# circuit-board.net
KiCad netlist of a schematic drawn in EAGLE
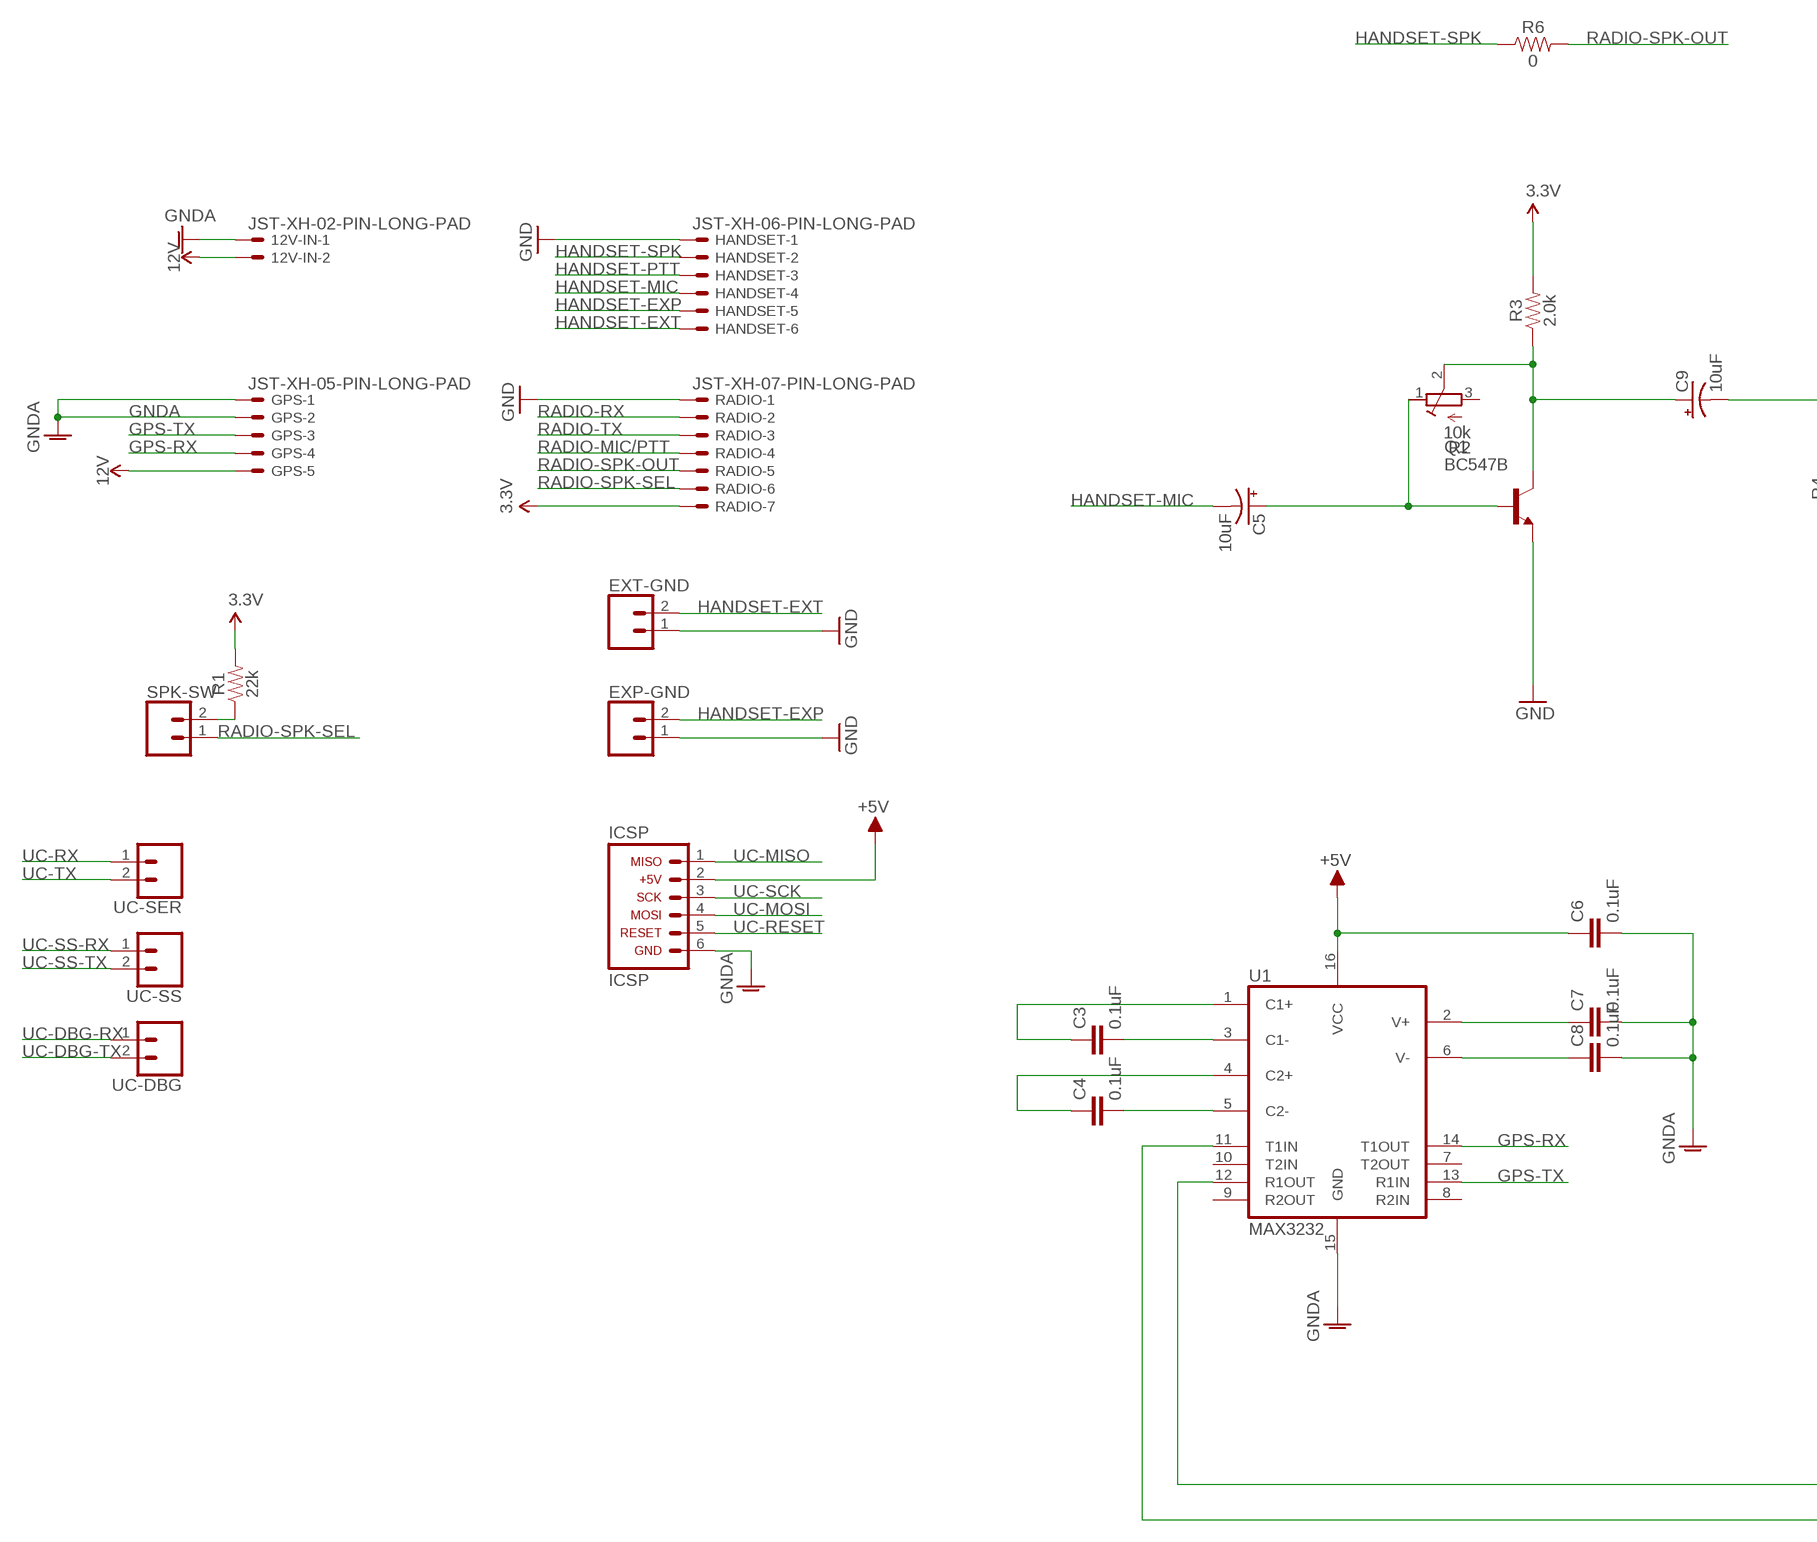
[diagram p0: schematic, sheet 1, part 1 of 2]
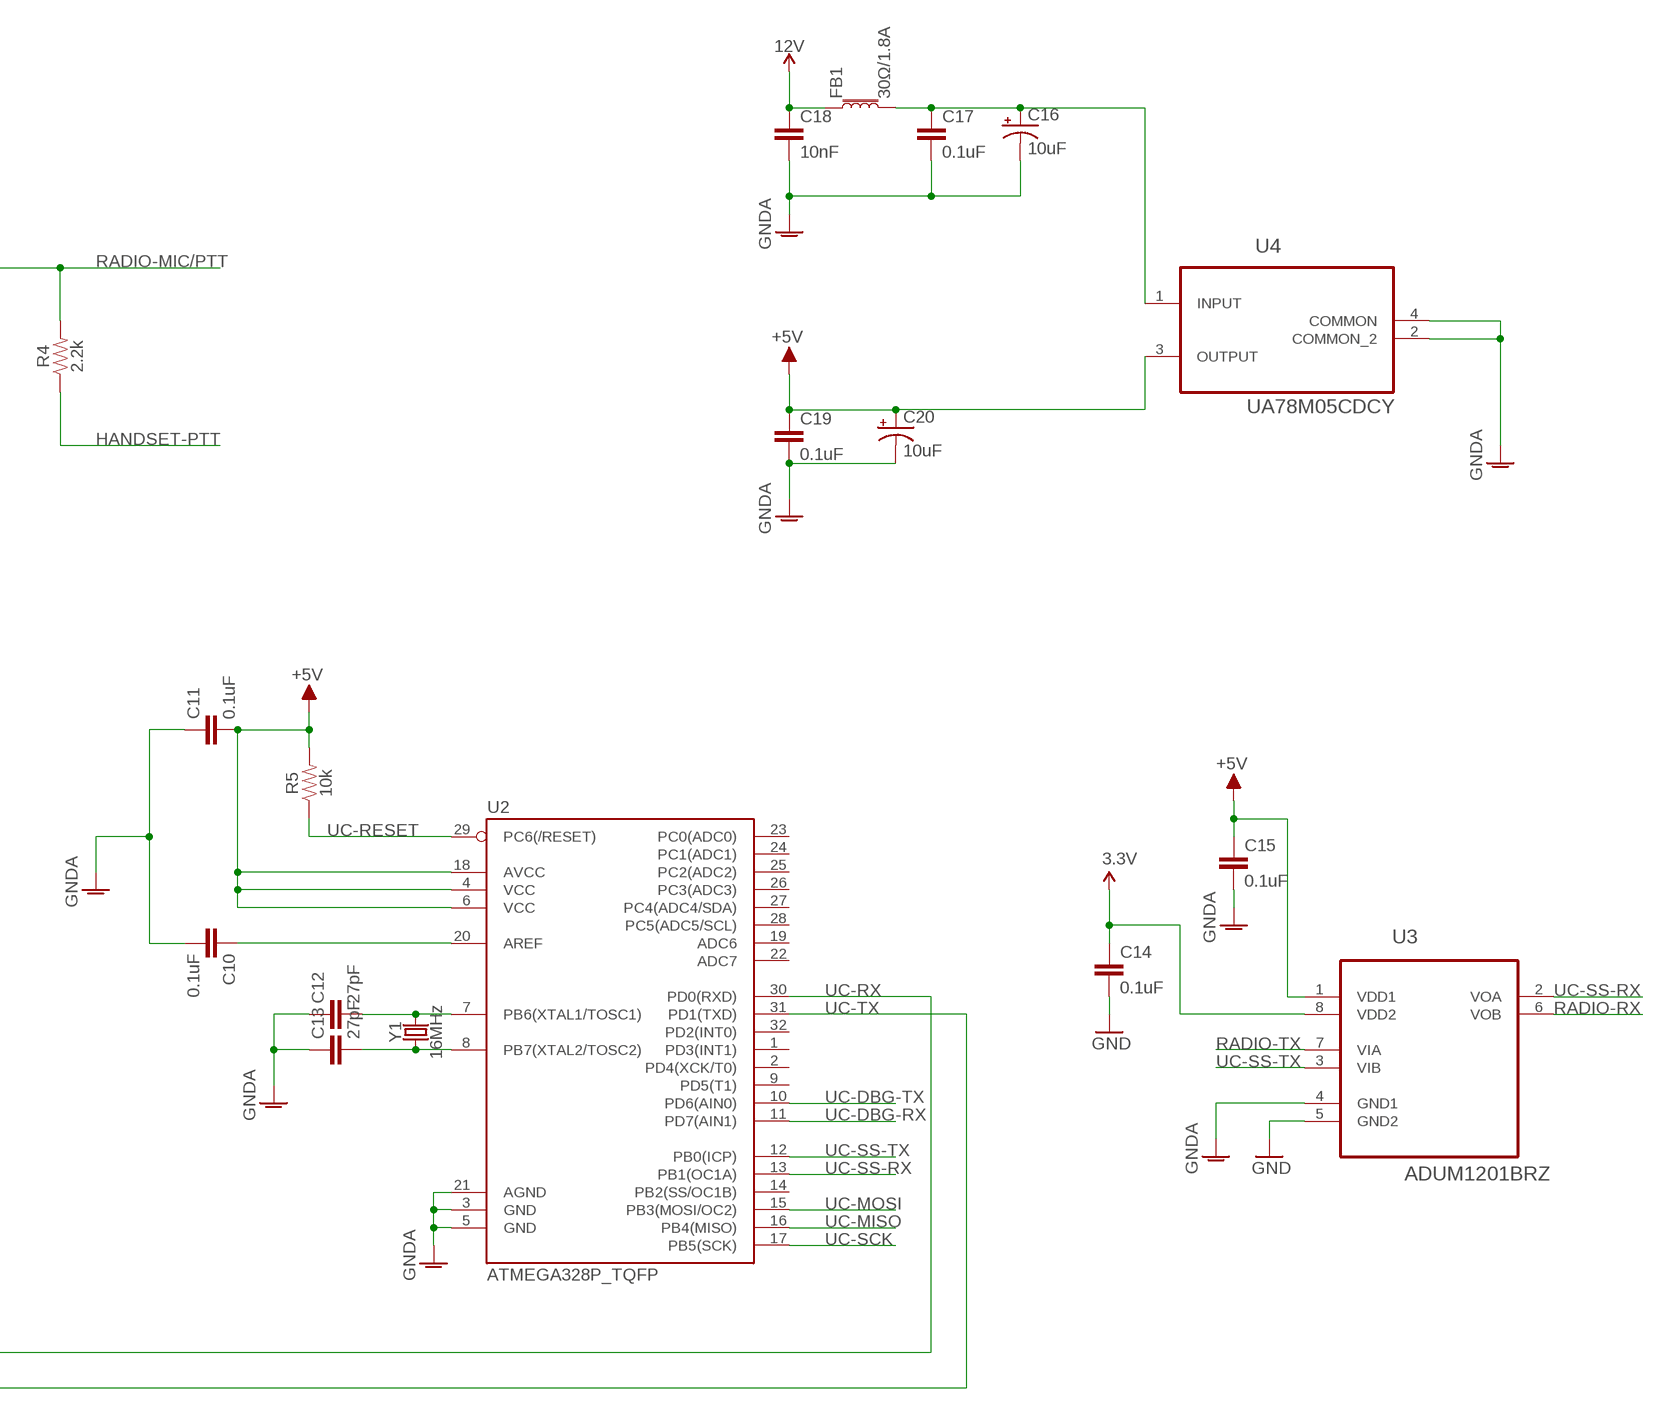
[diagram p1: schematic, sheet 1, part 2 of 2]

(export (version "E")
  (design (tool "Eeschema 10.0.6"))
  (components
    (comp (ref "12V-IN")
      (value "JST-XH-02-PIN-LONG-PAD")
      (footprint "eagle-import:JST-XH-02-PACKAGE-LONG-PAD")
      (libsource (lib "eagle-import") (part "JST-XH-02-PIN-LONG-PAD"))
    )
    (comp (ref "C3")
      (value "0.1uF")
      (footprint "eagle-import:0603")
      (libsource (lib "eagle-import") (part "0.1UF-0603-25V-5%"))
    )
    (comp (ref "C4")
      (value "0.1uF")
      (footprint "eagle-import:0603")
      (libsource (lib "eagle-import") (part "0.1UF-0603-25V-5%"))
    )
    (comp (ref "C5")
      (value "10uF")
      (footprint "eagle-import:E2,5-5")
      (libsource (lib "eagle-import") (part "CPOL-USE2.5-5"))
    )
    (comp (ref "C6")
      (value "0.1uF")
      (footprint "eagle-import:0603")
      (libsource (lib "eagle-import") (part "0.1UF-0603-25V-5%"))
    )
    (comp (ref "C7")
      (value "0.1uF")
      (footprint "eagle-import:0603")
      (libsource (lib "eagle-import") (part "0.1UF-0603-25V-5%"))
    )
    (comp (ref "C8")
      (value "0.1uF")
      (footprint "eagle-import:0603")
      (libsource (lib "eagle-import") (part "0.1UF-0603-25V-5%"))
    )
    (comp (ref "C9")
      (value "10uF")
      (footprint "eagle-import:E2,5-5")
      (libsource (lib "eagle-import") (part "CPOL-USE2.5-5"))
    )
    (comp (ref "C10")
      (value "0.1uF")
      (footprint "eagle-import:0603")
      (libsource (lib "eagle-import") (part "0.1UF-0603-25V-5%"))
    )
    (comp (ref "C11")
      (value "0.1uF")
      (footprint "eagle-import:0603")
      (libsource (lib "eagle-import") (part "0.1UF-0603-25V-5%"))
    )
    (comp (ref "C12")
      (value "27pF")
      (footprint "eagle-import:0603")
      (libsource (lib "eagle-import") (part "27PF-0603-50V-5%"))
    )
    (comp (ref "C13")
      (value "27pF")
      (footprint "eagle-import:0603")
      (libsource (lib "eagle-import") (part "27PF-0603-50V-5%"))
    )
    (comp (ref "C14")
      (value "0.1uF")
      (footprint "eagle-import:0603")
      (libsource (lib "eagle-import") (part "0.1UF-0603-25V-5%"))
    )
    (comp (ref "C15")
      (value "0.1uF")
      (footprint "eagle-import:0603")
      (libsource (lib "eagle-import") (part "0.1UF-0603-25V-5%"))
    )
    (comp (ref "C16")
      (value "10uF")
      (footprint "eagle-import:E2,5-5")
      (libsource (lib "eagle-import") (part "CPOL-USE2.5-5"))
    )
    (comp (ref "C17")
      (value "0.1uF")
      (footprint "eagle-import:0603")
      (libsource (lib "eagle-import") (part "0.1UF-0603-25V-5%"))
    )
    (comp (ref "C18")
      (value "10nF")
      (footprint "eagle-import:0603")
      (libsource (lib "eagle-import") (part "10NF-0603-50V-10%"))
    )
    (comp (ref "C19")
      (value "0.1uF")
      (footprint "eagle-import:0603")
      (libsource (lib "eagle-import") (part "0.1UF-0603-25V-5%"))
    )
    (comp (ref "C20")
      (value "10uF")
      (footprint "eagle-import:E2,5-5")
      (libsource (lib "eagle-import") (part "CPOL-USE2.5-5"))
    )
    (comp (ref "EXP-GND")
      (value "CONN_02")
      (footprint "eagle-import:1X02")
      (libsource (lib "eagle-import") (part "CONN_02"))
    )
    (comp (ref "EXT-GND")
      (value "CONN_02")
      (footprint "eagle-import:1X02")
      (libsource (lib "eagle-import") (part "CONN_02"))
    )
    (comp (ref "FB1")
      (value "30Ω/1.8A")
      (footprint "eagle-import:0603")
      (libsource (lib "eagle-import") (part "FERRITE_BEAD-0603"))
    )
    (comp (ref "GPS")
      (value "JST-XH-05-PIN-LONG-PAD")
      (footprint "eagle-import:JST-XH-05-PACKAGE-LONG-PAD")
      (libsource (lib "eagle-import") (part "JST-XH-05-PIN-LONG-PAD"))
    )
    (comp (ref "HANDSET")
      (value "JST-XH-06-PIN-LONG-PAD")
      (footprint "eagle-import:JST-XH-06-PACKAGE-LONG-PAD")
      (libsource (lib "eagle-import") (part "JST-XH-06-PIN-LONG-PAD"))
    )
    (comp (ref "ICSP")
      (value "ARDUINO_CONN-ICSP")
      (footprint "eagle-import:CONN-2X03")
      (libsource (lib "eagle-import") (part "ARDUINO_CONN-ICSP"))
    )
    (comp (ref "Q1")
      (value "BC547B")
      (footprint "eagle-import:TO92")
      (libsource (lib "eagle-import") (part "BC547B"))
    )
    (comp (ref "R1")
      (value "22k")
      (footprint "eagle-import:0603")
      (libsource (lib "eagle-import") (part "22KOHM-0603-1/10W-1%"))
    )
    (comp (ref "R2")
      (value "10k")
      (footprint "eagle-import:RTRIMT93YA")
      (libsource (lib "eagle-import") (part "R-TRIMMT93YA"))
    )
    (comp (ref "R3")
      (value "2.0k")
      (footprint "eagle-import:0603")
      (libsource (lib "eagle-import") (part "2.0KOHM-0603-1/10W-5%"))
    )
    (comp (ref "R4")
      (value "2.2k")
      (footprint "eagle-import:0603")
      (libsource (lib "eagle-import") (part "2.2KOHM-0603-1/10W-1%"))
    )
    (comp (ref "R5")
      (value "10k")
      (footprint "eagle-import:0603")
      (libsource (lib "eagle-import") (part "10KOHM-0603-1/10W-1%"))
    )
    (comp (ref "R6")
      (value "0")
      (footprint "eagle-import:0603")
      (libsource (lib "eagle-import") (part "0OHM-0603-1/10W-5%"))
    )
    (comp (ref "RADIO")
      (value "JST-XH-07-PIN-LONG-PAD")
      (footprint "eagle-import:JST-XH-07-PACKAGE-LONG-PAD")
      (libsource (lib "eagle-import") (part "JST-XH-07-PIN-LONG-PAD"))
    )
    (comp (ref "SPK-SW")
      (value "CONN_02")
      (footprint "eagle-import:1X02")
      (libsource (lib "eagle-import") (part "CONN_02"))
    )
    (comp (ref "U1")
      (value "MAX3232")
      (footprint "eagle-import:SO16")
      (libsource (lib "eagle-import") (part "MAX2323SOIC16"))
    )
    (comp (ref "U2")
      (value "ATMEGA328P_TQFP")
      (footprint "eagle-import:TQFP32-08")
      (libsource (lib "eagle-import") (part "ATMEGA328P_TQFP"))
    )
    (comp (ref "U3")
      (value "ADUM1201BRZ")
      (footprint "eagle-import:SOIC127P600X175-8N")
      (libsource (lib "eagle-import") (part "ADUM1201BRZ"))
    )
    (comp (ref "U4")
      (value "UA78M05CDCY")
      (footprint "eagle-import:SOT230P700X180-4N")
      (libsource (lib "eagle-import") (part "UA78M05CDCY"))
    )
    (comp (ref "UC-DBG")
      (value "CONN_02")
      (footprint "eagle-import:1X02")
      (libsource (lib "eagle-import") (part "CONN_02"))
    )
    (comp (ref "UC-SER")
      (value "CONN_02")
      (footprint "eagle-import:1X02")
      (libsource (lib "eagle-import") (part "CONN_02"))
    )
    (comp (ref "UC-SS")
      (value "CONN_02")
      (footprint "eagle-import:1X02")
      (libsource (lib "eagle-import") (part "CONN_02"))
    )
    (comp (ref "Y1")
      (value "16MHz")
      (footprint "eagle-import:HC49US")
      (libsource (lib "eagle-import") (part "CRYSTAL-16MHZPTH-HC49US"))
    )
  )
  (nets
    (net (code "1") (name "+5V") (class "Default")
      (node (ref "C11") (pin "2") (pinfunction "2_2") (pintype "passive"))
      (node (ref "C15") (pin "1") (pinfunction "1_1") (pintype "passive"))
      (node (ref "C19") (pin "1") (pinfunction "1_1") (pintype "passive"))
      (node (ref "C20") (pin "+") (pinfunction "+_+") (pintype "passive"))
      (node (ref "C6") (pin "1") (pinfunction "1_1") (pintype "passive"))
      (node (ref "ICSP") (pin "2") (pinfunction "2_2") (pintype "passive"))
      (node (ref "R5") (pin "2") (pinfunction "2_2") (pintype "passive"))
      (node (ref "U1") (pin "16") (pinfunction "VCC_16") (pintype "bidirectional"))
      (node (ref "U2") (pin "18") (pinfunction "AVCC_18") (pintype "bidirectional"))
      (node (ref "U2") (pin "4") (pinfunction "VCC_4") (pintype "bidirectional"))
      (node (ref "U2") (pin "6") (pinfunction "VCC_6") (pintype "bidirectional"))
      (node (ref "U3") (pin "1") (pinfunction "VDD1_1") (pintype "power_in"))
      (node (ref "U4") (pin "3") (pinfunction "OUTPUT_3") (pintype "input"))
    )
    (net (code "2") (name "/GPS-RX") (class "Default")
      (node (ref "GPS") (pin "4") (pinfunction "S_4") (pintype "passive"))
      (node (ref "U1") (pin "14") (pinfunction "T1OUT_14") (pintype "output"))
    )
    (net (code "3") (name "/GPS-TX") (class "Default")
      (node (ref "GPS") (pin "3") (pinfunction "S_3") (pintype "passive"))
      (node (ref "U1") (pin "13") (pinfunction "R1IN_13") (pintype "input"))
    )
    (net (code "4") (name "/HANDSET-EXP") (class "Default")
      (node (ref "EXP-GND") (pin "2") (pinfunction "2_2") (pintype "passive"))
      (node (ref "HANDSET") (pin "5") (pinfunction "S_5") (pintype "passive"))
    )
    (net (code "5") (name "/HANDSET-EXT") (class "Default")
      (node (ref "EXT-GND") (pin "2") (pinfunction "2_2") (pintype "passive"))
      (node (ref "HANDSET") (pin "6") (pinfunction "S_6") (pintype "passive"))
    )
    (net (code "6") (name "/HANDSET-MIC") (class "Default")
      (node (ref "C5") (pin "-") (pinfunction "-_-") (pintype "passive"))
      (node (ref "HANDSET") (pin "4") (pinfunction "S_4") (pintype "passive"))
    )
    (net (code "7") (name "/HANDSET-PTT") (class "Default")
      (node (ref "HANDSET") (pin "3") (pinfunction "S_3") (pintype "passive"))
      (node (ref "R4") (pin "1") (pinfunction "1_1") (pintype "passive"))
    )
    (net (code "8") (name "/HANDSET-SPK") (class "Default")
      (node (ref "HANDSET") (pin "2") (pinfunction "S_2") (pintype "passive"))
      (node (ref "R6") (pin "1") (pinfunction "1_1") (pintype "passive"))
    )
    (net (code "9") (name "/RADIO-MIC{slash}PTT") (class "Default")
      (node (ref "C9") (pin "-") (pinfunction "-_-") (pintype "passive"))
      (node (ref "R4") (pin "2") (pinfunction "2_2") (pintype "passive"))
      (node (ref "RADIO") (pin "4") (pinfunction "S_4") (pintype "passive"))
    )
    (net (code "10") (name "/RADIO-RX") (class "Default")
      (node (ref "RADIO") (pin "2") (pinfunction "S_2") (pintype "passive"))
      (node (ref "U3") (pin "6") (pinfunction "VOB_6") (pintype "output"))
    )
    (net (code "11") (name "/RADIO-SPK-OUT") (class "Default")
      (node (ref "R6") (pin "2") (pinfunction "2_2") (pintype "passive"))
      (node (ref "RADIO") (pin "5") (pinfunction "S_5") (pintype "passive"))
    )
    (net (code "12") (name "/RADIO-SPK-SEL") (class "Default")
      (node (ref "RADIO") (pin "6") (pinfunction "S_6") (pintype "passive"))
      (node (ref "SPK-SW") (pin "1") (pinfunction "1_1") (pintype "passive"))
    )
    (net (code "13") (name "/RADIO-TX") (class "Default")
      (node (ref "RADIO") (pin "3") (pinfunction "S_3") (pintype "passive"))
      (node (ref "U3") (pin "7") (pinfunction "VIA_7") (pintype "input"))
    )
    (net (code "14") (name "/UC-DBG-RX") (class "Default")
      (node (ref "U2") (pin "11") (pinfunction "PD7(AIN1)_11") (pintype "bidirectional"))
      (node (ref "UC-DBG") (pin "1") (pinfunction "1_1") (pintype "passive"))
    )
    (net (code "15") (name "/UC-DBG-TX") (class "Default")
      (node (ref "U2") (pin "10") (pinfunction "PD6(AIN0)_10") (pintype "bidirectional"))
      (node (ref "UC-DBG") (pin "2") (pinfunction "2_2") (pintype "passive"))
    )
    (net (code "16") (name "/UC-MISO") (class "Default")
      (node (ref "ICSP") (pin "1") (pinfunction "1_1") (pintype "passive"))
      (node (ref "U2") (pin "16") (pinfunction "PB4(MISO)_16") (pintype "bidirectional"))
    )
    (net (code "17") (name "/UC-MOSI") (class "Default")
      (node (ref "ICSP") (pin "4") (pinfunction "4_4") (pintype "passive"))
      (node (ref "U2") (pin "15") (pinfunction "PB3(MOSI/OC2)_15") (pintype "bidirectional"))
    )
    (net (code "18") (name "/UC-RESET") (class "Default")
      (node (ref "ICSP") (pin "5") (pinfunction "5_5") (pintype "passive"))
      (node (ref "R5") (pin "1") (pinfunction "1_1") (pintype "passive"))
      (node (ref "U2") (pin "29") (pinfunction "PC6(/RESET)_29") (pintype "bidirectional"))
    )
    (net (code "19") (name "/UC-RX") (class "Default")
      (node (ref "U1") (pin "12") (pinfunction "R1OUT_12") (pintype "output"))
      (node (ref "U2") (pin "30") (pinfunction "PD0(RXD)_30") (pintype "bidirectional"))
      (node (ref "UC-SER") (pin "1") (pinfunction "1_1") (pintype "passive"))
    )
    (net (code "20") (name "/UC-SCK") (class "Default")
      (node (ref "ICSP") (pin "3") (pinfunction "3_3") (pintype "passive"))
      (node (ref "U2") (pin "17") (pinfunction "PB5(SCK)_17") (pintype "bidirectional"))
    )
    (net (code "21") (name "/UC-SS-RX") (class "Default")
      (node (ref "U2") (pin "13") (pinfunction "PB1(OC1A)_13") (pintype "bidirectional"))
      (node (ref "U3") (pin "2") (pinfunction "VOA_2") (pintype "output"))
      (node (ref "UC-SS") (pin "1") (pinfunction "1_1") (pintype "passive"))
    )
    (net (code "22") (name "/UC-SS-TX") (class "Default")
      (node (ref "U2") (pin "12") (pinfunction "PB0(ICP)_12") (pintype "bidirectional"))
      (node (ref "U3") (pin "3") (pinfunction "VIB_3") (pintype "input"))
      (node (ref "UC-SS") (pin "2") (pinfunction "2_2") (pintype "passive"))
    )
    (net (code "23") (name "/UC-TX") (class "Default")
      (node (ref "U1") (pin "11") (pinfunction "T1IN_11") (pintype "input"))
      (node (ref "U2") (pin "31") (pinfunction "PD1(TXD)_31") (pintype "bidirectional"))
      (node (ref "UC-SER") (pin "2") (pinfunction "2_2") (pintype "passive"))
    )
    (net (code "24") (name "3.3V") (class "Default")
      (node (ref "C14") (pin "1") (pinfunction "1_1") (pintype "passive"))
      (node (ref "R1") (pin "2") (pinfunction "2_2") (pintype "passive"))
      (node (ref "R3") (pin "2") (pinfunction "2_2") (pintype "passive"))
      (node (ref "RADIO") (pin "7") (pinfunction "S_7") (pintype "passive"))
      (node (ref "U3") (pin "8") (pinfunction "VDD2_8") (pintype "power_in"))
    )
    (net (code "25") (name "12V") (class "Default")
      (node (ref "12V-IN") (pin "2") (pinfunction "S_2") (pintype "passive"))
      (node (ref "C18") (pin "1") (pinfunction "1_1") (pintype "passive"))
      (node (ref "FB1") (pin "1") (pinfunction "1_1") (pintype "passive"))
      (node (ref "GPS") (pin "5") (pinfunction "S_5") (pintype "passive"))
    )
    (net (code "26") (name "GND") (class "Default")
      (node (ref "C14") (pin "2") (pinfunction "2_2") (pintype "passive"))
      (node (ref "EXP-GND") (pin "1") (pinfunction "1_1") (pintype "passive"))
      (node (ref "EXT-GND") (pin "1") (pinfunction "1_1") (pintype "passive"))
      (node (ref "HANDSET") (pin "1") (pinfunction "S_1") (pintype "passive"))
      (node (ref "Q1") (pin "1") (pinfunction "E_1") (pintype "passive"))
      (node (ref "RADIO") (pin "1") (pinfunction "S_1") (pintype "passive"))
      (node (ref "U3") (pin "5") (pinfunction "GND2_5") (pintype "passive"))
    )
    (net (code "27") (name "GNDA") (class "Default")
      (node (ref "12V-IN") (pin "1") (pinfunction "S_1") (pintype "passive"))
      (node (ref "C10") (pin "2") (pinfunction "2_2") (pintype "passive"))
      (node (ref "C11") (pin "1") (pinfunction "1_1") (pintype "passive"))
      (node (ref "C12") (pin "1") (pinfunction "1_1") (pintype "passive"))
      (node (ref "C13") (pin "1") (pinfunction "1_1") (pintype "passive"))
      (node (ref "C15") (pin "2") (pinfunction "2_2") (pintype "passive"))
      (node (ref "C16") (pin "-") (pinfunction "-_-") (pintype "passive"))
      (node (ref "C17") (pin "2") (pinfunction "2_2") (pintype "passive"))
      (node (ref "C18") (pin "2") (pinfunction "2_2") (pintype "passive"))
      (node (ref "C19") (pin "2") (pinfunction "2_2") (pintype "passive"))
      (node (ref "C20") (pin "-") (pinfunction "-_-") (pintype "passive"))
      (node (ref "C6") (pin "2") (pinfunction "2_2") (pintype "passive"))
      (node (ref "C7") (pin "2") (pinfunction "2_2") (pintype "passive"))
      (node (ref "C8") (pin "2") (pinfunction "2_2") (pintype "passive"))
      (node (ref "GPS") (pin "1") (pinfunction "S_1") (pintype "passive"))
      (node (ref "GPS") (pin "2") (pinfunction "S_2") (pintype "passive"))
      (node (ref "ICSP") (pin "6") (pinfunction "6_6") (pintype "passive"))
      (node (ref "U1") (pin "15") (pinfunction "GND_15") (pintype "bidirectional"))
      (node (ref "U2") (pin "21") (pinfunction "AGND_21") (pintype "bidirectional"))
      (node (ref "U2") (pin "3") (pinfunction "GND_3") (pintype "bidirectional"))
      (node (ref "U2") (pin "5") (pinfunction "GND_5") (pintype "bidirectional"))
      (node (ref "U3") (pin "4") (pinfunction "GND1_4") (pintype "passive"))
      (node (ref "U4") (pin "2") (pinfunction "COMMON_2_2") (pintype "output"))
      (node (ref "U4") (pin "4") (pinfunction "COMMON_4") (pintype "output"))
    )
    (net (code "28") (name "Net-(Q1-B)") (class "Default")
      (node (ref "C5") (pin "+") (pinfunction "+_+") (pintype "passive"))
      (node (ref "Q1") (pin "2") (pinfunction "B_2") (pintype "passive"))
      (node (ref "R2") (pin "1") (pinfunction "E_1") (pintype "passive"))
    )
    (net (code "29") (name "Net-(Q1-C)") (class "Default")
      (node (ref "C9") (pin "+") (pinfunction "+_+") (pintype "passive"))
      (node (ref "Q1") (pin "3") (pinfunction "C_3") (pintype "passive"))
      (node (ref "R2") (pin "2") (pinfunction "S_2") (pintype "passive"))
      (node (ref "R3") (pin "1") (pinfunction "1_1") (pintype "passive"))
    )
    (net (code "30") (name "Net-(R1-Pad1)") (class "Default")
      (node (ref "R1") (pin "1") (pinfunction "1_1") (pintype "passive"))
      (node (ref "SPK-SW") (pin "2") (pinfunction "2_2") (pintype "passive"))
    )
    (net (code "31") (name "Net-(U1-C1+)") (class "Default")
      (node (ref "C3") (pin "1") (pinfunction "1_1") (pintype "passive"))
      (node (ref "U1") (pin "1") (pinfunction "C1+_1") (pintype "bidirectional"))
    )
    (net (code "32") (name "Net-(U1-C1-)") (class "Default")
      (node (ref "C3") (pin "2") (pinfunction "2_2") (pintype "passive"))
      (node (ref "U1") (pin "3") (pinfunction "C1-_3") (pintype "bidirectional"))
    )
    (net (code "33") (name "Net-(U1-C2+)") (class "Default")
      (node (ref "C4") (pin "1") (pinfunction "1_1") (pintype "passive"))
      (node (ref "U1") (pin "4") (pinfunction "C2+_4") (pintype "bidirectional"))
    )
    (net (code "34") (name "Net-(U1-C2-)") (class "Default")
      (node (ref "C4") (pin "2") (pinfunction "2_2") (pintype "passive"))
      (node (ref "U1") (pin "5") (pinfunction "C2-_5") (pintype "bidirectional"))
    )
    (net (code "35") (name "Net-(U1-V+)") (class "Default")
      (node (ref "C7") (pin "1") (pinfunction "1_1") (pintype "passive"))
      (node (ref "U1") (pin "2") (pinfunction "V+_2") (pintype "bidirectional"))
    )
    (net (code "36") (name "Net-(U1-V-)") (class "Default")
      (node (ref "C8") (pin "1") (pinfunction "1_1") (pintype "passive"))
      (node (ref "U1") (pin "6") (pinfunction "V-_6") (pintype "bidirectional"))
    )
    (net (code "37") (name "Net-(U2-AREF)") (class "Default")
      (node (ref "C10") (pin "1") (pinfunction "1_1") (pintype "passive"))
      (node (ref "U2") (pin "20") (pinfunction "AREF_20") (pintype "bidirectional"))
    )
    (net (code "38") (name "Net-(U2-PB6(XTAL1{slash}TOSC1))") (class "Default")
      (node (ref "C12") (pin "2") (pinfunction "2_2") (pintype "passive"))
      (node (ref "U2") (pin "7") (pinfunction "PB6(XTAL1/TOSC1)_7") (pintype "bidirectional"))
      (node (ref "Y1") (pin "2") (pinfunction "2_2") (pintype "passive"))
    )
    (net (code "39") (name "Net-(U2-PB7(XTAL2{slash}TOSC2))") (class "Default")
      (node (ref "C13") (pin "2") (pinfunction "2_2") (pintype "passive"))
      (node (ref "U2") (pin "8") (pinfunction "PB7(XTAL2/TOSC2)_8") (pintype "bidirectional"))
      (node (ref "Y1") (pin "1") (pinfunction "1_1") (pintype "passive"))
    )
    (net (code "40") (name "Net-(U4-INPUT)") (class "Default")
      (node (ref "C16") (pin "+") (pinfunction "+_+") (pintype "passive"))
      (node (ref "C17") (pin "1") (pinfunction "1_1") (pintype "passive"))
      (node (ref "FB1") (pin "2") (pinfunction "2_2") (pintype "passive"))
      (node (ref "U4") (pin "1") (pinfunction "INPUT_1") (pintype "input"))
    )
    (net (code "41") (name "unconnected-(R2-A-Pad3)") (class "Default")
      (node (ref "R2") (pin "3") (pinfunction "A_3") (pintype "passive"))
    )
    (net (code "42") (name "unconnected-(U1-R2IN-Pad8)") (class "Default")
      (node (ref "U1") (pin "8") (pinfunction "R2IN_8") (pintype "input"))
    )
    (net (code "43") (name "unconnected-(U1-R2OUT-Pad9)") (class "Default")
      (node (ref "U1") (pin "9") (pinfunction "R2OUT_9") (pintype "output"))
    )
    (net (code "44") (name "unconnected-(U1-T2IN-Pad10)") (class "Default")
      (node (ref "U1") (pin "10") (pinfunction "T2IN_10") (pintype "input"))
    )
    (net (code "45") (name "unconnected-(U1-T2OUT-Pad7)") (class "Default")
      (node (ref "U1") (pin "7") (pinfunction "T2OUT_7") (pintype "output"))
    )
    (net (code "46") (name "unconnected-(U2-ADC6-Pad19)") (class "Default")
      (node (ref "U2") (pin "19") (pinfunction "ADC6_19") (pintype "bidirectional"))
    )
    (net (code "47") (name "unconnected-(U2-ADC7-Pad22)") (class "Default")
      (node (ref "U2") (pin "22") (pinfunction "ADC7_22") (pintype "bidirectional"))
    )
    (net (code "48") (name "unconnected-(U2-PB2(SS{slash}OC1B)-Pad14)") (class "Default")
      (node (ref "U2") (pin "14") (pinfunction "PB2(SS/OC1B)_14") (pintype "bidirectional"))
    )
    (net (code "49") (name "unconnected-(U2-PC0(ADC0)-Pad23)") (class "Default")
      (node (ref "U2") (pin "23") (pinfunction "PC0(ADC0)_23") (pintype "bidirectional"))
    )
    (net (code "50") (name "unconnected-(U2-PC1(ADC1)-Pad24)") (class "Default")
      (node (ref "U2") (pin "24") (pinfunction "PC1(ADC1)_24") (pintype "bidirectional"))
    )
    (net (code "51") (name "unconnected-(U2-PC2(ADC2)-Pad25)") (class "Default")
      (node (ref "U2") (pin "25") (pinfunction "PC2(ADC2)_25") (pintype "bidirectional"))
    )
    (net (code "52") (name "unconnected-(U2-PC3(ADC3)-Pad26)") (class "Default")
      (node (ref "U2") (pin "26") (pinfunction "PC3(ADC3)_26") (pintype "bidirectional"))
    )
    (net (code "53") (name "unconnected-(U2-PC4(ADC4{slash}SDA)-Pad27)") (class "Default")
      (node (ref "U2") (pin "27") (pinfunction "PC4(ADC4/SDA)_27") (pintype "bidirectional"))
    )
    (net (code "54") (name "unconnected-(U2-PC5(ADC5{slash}SCL)-Pad28)") (class "Default")
      (node (ref "U2") (pin "28") (pinfunction "PC5(ADC5/SCL)_28") (pintype "bidirectional"))
    )
    (net (code "55") (name "unconnected-(U2-PD2(INT0)-Pad32)") (class "Default")
      (node (ref "U2") (pin "32") (pinfunction "PD2(INT0)_32") (pintype "bidirectional"))
    )
    (net (code "56") (name "unconnected-(U2-PD3(INT1)-Pad1)") (class "Default")
      (node (ref "U2") (pin "1") (pinfunction "PD3(INT1)_1") (pintype "bidirectional"))
    )
    (net (code "57") (name "unconnected-(U2-PD4(XCK{slash}T0)-Pad2)") (class "Default")
      (node (ref "U2") (pin "2") (pinfunction "PD4(XCK/T0)_2") (pintype "bidirectional"))
    )
    (net (code "58") (name "unconnected-(U2-PD5(T1)-Pad9)") (class "Default")
      (node (ref "U2") (pin "9") (pinfunction "PD5(T1)_9") (pintype "bidirectional"))
    )
  )
)
